# TERM.net
KiCad netlist of a schematic drawn in Altium Designer
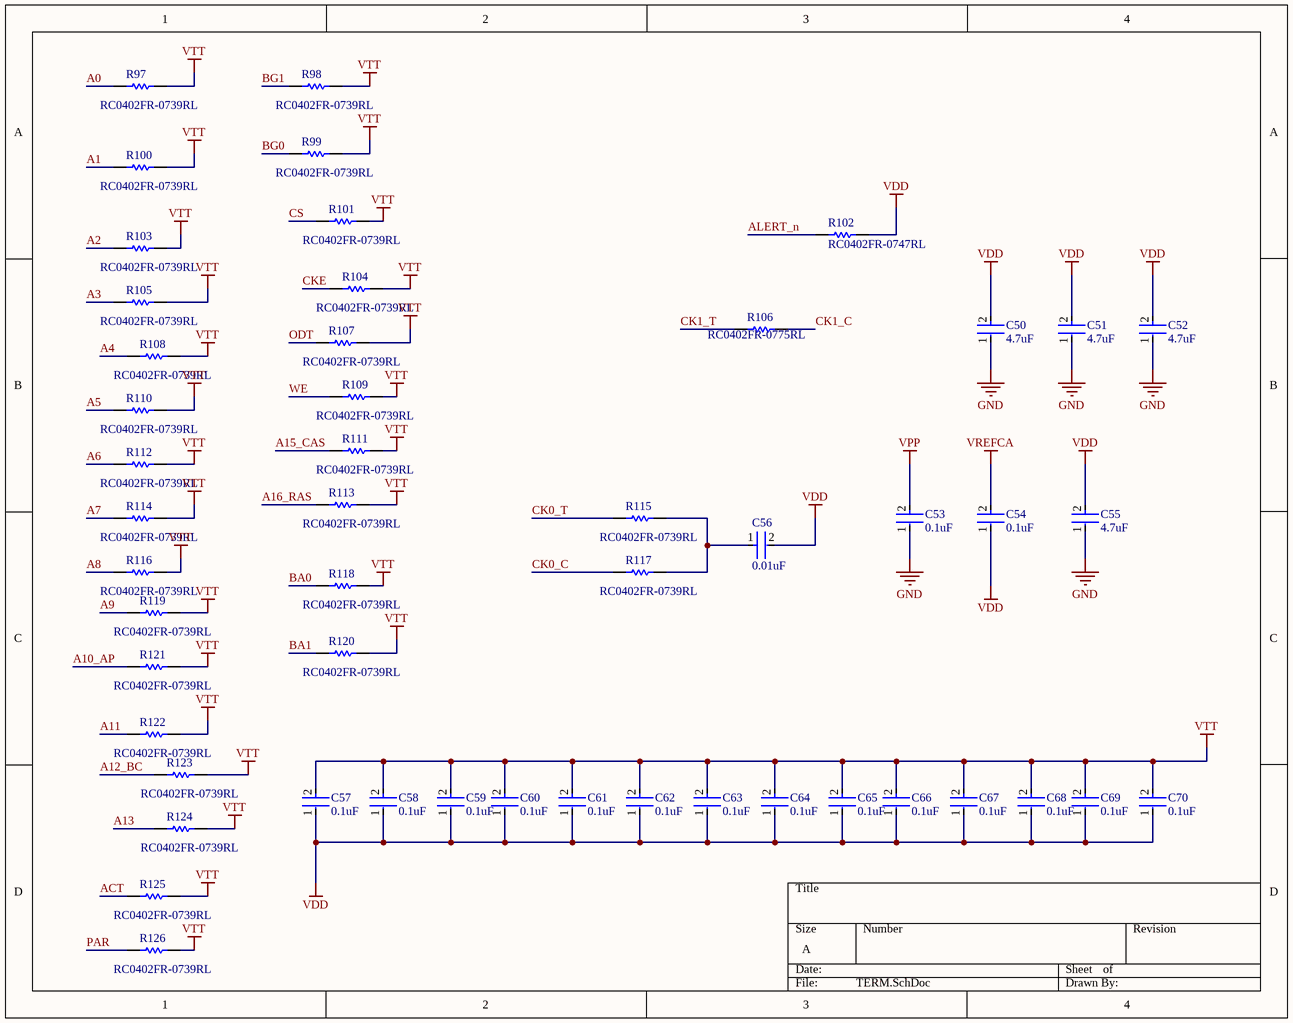
[diagram p0: TERM.SchDoc]

(export (version "E")
  (design (tool "Eeschema 10.0.6"))
  (components
    (comp (ref "C50")
      (value "4.7uF")
      (footprint "FP-C1608-080-0_1-IPC_C")
      (description "Multilayer Ceramic Capacitors 4.7μF ±10% 16V X5R SMD 0603")
      (fields (field (name "TOLERANCE") "10%") (field (name "VOLTAGE") "16V"))
      (libsource (lib "Altium Content Vault") (part "236180d848d6139a670b325ea6854c9"))
    )
    (comp (ref "C51")
      (value "4.7uF")
      (footprint "FP-C1608-080-0_1-IPC_C")
      (description "Multilayer Ceramic Capacitors 4.7μF ±10% 16V X5R SMD 0603")
      (fields (field (name "TOLERANCE") "10%") (field (name "VOLTAGE") "16V"))
      (libsource (lib "Altium Content Vault") (part "236180d848d6139a670b325ea6854c9"))
    )
    (comp (ref "C52")
      (value "4.7uF")
      (footprint "FP-C1608-080-0_1-IPC_C")
      (description "Multilayer Ceramic Capacitors 4.7μF ±10% 16V X5R SMD 0603")
      (fields (field (name "TOLERANCE") "10%") (field (name "VOLTAGE") "16V"))
      (libsource (lib "Altium Content Vault") (part "236180d848d6139a670b325ea6854c9"))
    )
    (comp (ref "C53")
      (value "0.1uF")
      (footprint "FP-GRM15-MFG")
      (description "CAP CER 0.1UF 16V X7R 0402")
      (fields (field (name "MANUFACTURER PART NUMBER") "GRM155R71C104KA88D") (field (name "TOLERANCE") "10%"))
      (libsource (lib "Altium Content Vault") (part "236180d848d6139a670b325ea6854c9"))
    )
    (comp (ref "C54")
      (value "0.1uF")
      (footprint "FP-GRM15-MFG")
      (description "CAP CER 0.1UF 16V X7R 0402")
      (fields (field (name "MANUFACTURER PART NUMBER") "GRM155R71C104KA88D") (field (name "TOLERANCE") "10%"))
      (libsource (lib "Altium Content Vault") (part "236180d848d6139a670b325ea6854c9"))
    )
    (comp (ref "C55")
      (value "4.7uF")
      (footprint "FP-C1608-080-0_1-IPC_C")
      (description "Multilayer Ceramic Capacitors 4.7μF ±10% 16V X5R SMD 0603")
      (fields (field (name "TOLERANCE") "10%") (field (name "VOLTAGE") "16V"))
      (libsource (lib "Altium Content Vault") (part "236180d848d6139a670b325ea6854c9"))
    )
    (comp (ref "C56")
      (value "0.01uF")
      (footprint "FP-GRM155-0_05-IPC_C")
      (description "Chip Multilayer Ceramic Capacitors for General Purpose, 0402, 10000pF, X7R, 15%, 10%, 50V")
      (fields (field (name "TOLERANCE") "10%") (field (name "VOLTAGE") "25V"))
      (libsource (lib "Altium Content Vault") (part "02cd4be3c70576c341d710602a673aa"))
    )
    (comp (ref "C57")
      (value "0.1uF")
      (footprint "FP-GRM15-MFG")
      (description "CAP CER 0.1UF 16V X7R 0402")
      (fields (field (name "MANUFACTURER PART NUMBER") "GRM155R71C104KA88D") (field (name "TOLERANCE") "10%"))
      (libsource (lib "Altium Content Vault") (part "236180d848d6139a670b325ea6854c9"))
    )
    (comp (ref "C58")
      (value "0.1uF")
      (footprint "FP-GRM15-MFG")
      (description "CAP CER 0.1UF 16V X7R 0402")
      (fields (field (name "MANUFACTURER PART NUMBER") "GRM155R71C104KA88D") (field (name "TOLERANCE") "10%"))
      (libsource (lib "Altium Content Vault") (part "236180d848d6139a670b325ea6854c9"))
    )
    (comp (ref "C59")
      (value "0.1uF")
      (footprint "FP-GRM15-MFG")
      (description "CAP CER 0.1UF 16V X7R 0402")
      (fields (field (name "MANUFACTURER PART NUMBER") "GRM155R71C104KA88D") (field (name "TOLERANCE") "10%"))
      (libsource (lib "Altium Content Vault") (part "236180d848d6139a670b325ea6854c9"))
    )
    (comp (ref "C60")
      (value "0.1uF")
      (footprint "FP-GRM15-MFG")
      (description "CAP CER 0.1UF 16V X7R 0402")
      (fields (field (name "MANUFACTURER PART NUMBER") "GRM155R71C104KA88D") (field (name "TOLERANCE") "10%"))
      (libsource (lib "Altium Content Vault") (part "236180d848d6139a670b325ea6854c9"))
    )
    (comp (ref "C61")
      (value "0.1uF")
      (footprint "FP-GRM15-MFG")
      (description "CAP CER 0.1UF 16V X7R 0402")
      (fields (field (name "MANUFACTURER PART NUMBER") "GRM155R71C104KA88D") (field (name "TOLERANCE") "10%"))
      (libsource (lib "Altium Content Vault") (part "236180d848d6139a670b325ea6854c9"))
    )
    (comp (ref "C62")
      (value "0.1uF")
      (footprint "FP-GRM15-MFG")
      (description "CAP CER 0.1UF 16V X7R 0402")
      (fields (field (name "MANUFACTURER PART NUMBER") "GRM155R71C104KA88D") (field (name "TOLERANCE") "10%"))
      (libsource (lib "Altium Content Vault") (part "236180d848d6139a670b325ea6854c9"))
    )
    (comp (ref "C63")
      (value "0.1uF")
      (footprint "FP-GRM15-MFG")
      (description "CAP CER 0.1UF 16V X7R 0402")
      (fields (field (name "MANUFACTURER PART NUMBER") "GRM155R71C104KA88D") (field (name "TOLERANCE") "10%"))
      (libsource (lib "Altium Content Vault") (part "236180d848d6139a670b325ea6854c9"))
    )
    (comp (ref "C64")
      (value "0.1uF")
      (footprint "FP-GRM15-MFG")
      (description "CAP CER 0.1UF 16V X7R 0402")
      (fields (field (name "MANUFACTURER PART NUMBER") "GRM155R71C104KA88D") (field (name "TOLERANCE") "10%"))
      (libsource (lib "Altium Content Vault") (part "236180d848d6139a670b325ea6854c9"))
    )
    (comp (ref "C65")
      (value "0.1uF")
      (footprint "FP-GRM15-MFG")
      (description "CAP CER 0.1UF 16V X7R 0402")
      (fields (field (name "MANUFACTURER PART NUMBER") "GRM155R71C104KA88D") (field (name "TOLERANCE") "10%"))
      (libsource (lib "Altium Content Vault") (part "236180d848d6139a670b325ea6854c9"))
    )
    (comp (ref "C66")
      (value "0.1uF")
      (footprint "FP-GRM15-MFG")
      (description "CAP CER 0.1UF 16V X7R 0402")
      (fields (field (name "MANUFACTURER PART NUMBER") "GRM155R71C104KA88D") (field (name "TOLERANCE") "10%"))
      (libsource (lib "Altium Content Vault") (part "236180d848d6139a670b325ea6854c9"))
    )
    (comp (ref "C67")
      (value "0.1uF")
      (footprint "FP-GRM15-MFG")
      (description "CAP CER 0.1UF 16V X7R 0402")
      (fields (field (name "MANUFACTURER PART NUMBER") "GRM155R71C104KA88D") (field (name "TOLERANCE") "10%"))
      (libsource (lib "Altium Content Vault") (part "236180d848d6139a670b325ea6854c9"))
    )
    (comp (ref "C68")
      (value "0.1uF")
      (footprint "FP-GRM15-MFG")
      (description "CAP CER 0.1UF 16V X7R 0402")
      (fields (field (name "MANUFACTURER PART NUMBER") "GRM155R71C104KA88D") (field (name "TOLERANCE") "10%"))
      (libsource (lib "Altium Content Vault") (part "236180d848d6139a670b325ea6854c9"))
    )
    (comp (ref "C69")
      (value "0.1uF")
      (footprint "FP-GRM15-MFG")
      (description "CAP CER 0.1UF 16V X7R 0402")
      (fields (field (name "MANUFACTURER PART NUMBER") "GRM155R71C104KA88D") (field (name "TOLERANCE") "10%"))
      (libsource (lib "Altium Content Vault") (part "236180d848d6139a670b325ea6854c9"))
    )
    (comp (ref "C70")
      (value "0.1uF")
      (footprint "FP-GRM15-MFG")
      (description "CAP CER 0.1UF 16V X7R 0402")
      (fields (field (name "MANUFACTURER PART NUMBER") "GRM155R71C104KA88D") (field (name "TOLERANCE") "10%"))
      (libsource (lib "Altium Content Vault") (part "236180d848d6139a670b325ea6854c9"))
    )
    (comp (ref "R97")
      (value "RC0402FR-0739RL")
      (footprint "RESC1005X40X25LL05T10")
      (fields (field (name "MANUFACTURER") "Yageo / Phycomp"))
      (libsource (lib "Altium Content Vault") (part "RES"))
    )
    (comp (ref "R98")
      (value "RC0402FR-0739RL")
      (footprint "RESC1005X40X25LL05T10")
      (fields (field (name "MANUFACTURER") "Yageo / Phycomp"))
      (libsource (lib "Altium Content Vault") (part "RES"))
    )
    (comp (ref "R99")
      (value "RC0402FR-0739RL")
      (footprint "RESC1005X40X25LL05T10")
      (fields (field (name "MANUFACTURER") "Yageo / Phycomp"))
      (libsource (lib "Altium Content Vault") (part "RES"))
    )
    (comp (ref "R100")
      (value "RC0402FR-0739RL")
      (footprint "RESC1005X40X25LL05T10")
      (fields (field (name "MANUFACTURER") "Yageo / Phycomp"))
      (libsource (lib "Altium Content Vault") (part "RES"))
    )
    (comp (ref "R101")
      (value "RC0402FR-0739RL")
      (footprint "RESC1005X40X25LL05T10")
      (fields (field (name "MANUFACTURER") "Yageo / Phycomp"))
      (libsource (lib "Altium Content Vault") (part "RES"))
    )
    (comp (ref "R102")
      (value "RC0402FR-0747RL")
      (footprint "RESC1005X40X25LL05T10")
      (fields (field (name "MANUFACTURER") "Yageo / Phycomp"))
      (libsource (lib "Altium Content Vault") (part "RES"))
    )
    (comp (ref "R103")
      (value "RC0402FR-0739RL")
      (footprint "RESC1005X40X25LL05T10")
      (fields (field (name "MANUFACTURER") "Yageo / Phycomp"))
      (libsource (lib "Altium Content Vault") (part "RES"))
    )
    (comp (ref "R104")
      (value "RC0402FR-0739RL")
      (footprint "RESC1005X40X25LL05T10")
      (fields (field (name "MANUFACTURER") "Yageo / Phycomp"))
      (libsource (lib "Altium Content Vault") (part "RES"))
    )
    (comp (ref "R105")
      (value "RC0402FR-0739RL")
      (footprint "RESC1005X40X25LL05T10")
      (fields (field (name "MANUFACTURER") "Yageo / Phycomp"))
      (libsource (lib "Altium Content Vault") (part "RES"))
    )
    (comp (ref "R106")
      (value "RC0402FR-0775RL")
      (footprint "RESC1005X40X25LL05T10")
      (fields (field (name "MANUFACTURER") "Yageo / Phycomp"))
      (libsource (lib "Altium Content Vault") (part "RES"))
    )
    (comp (ref "R107")
      (value "RC0402FR-0739RL")
      (footprint "RESC1005X40X25LL05T10")
      (fields (field (name "MANUFACTURER") "Yageo / Phycomp"))
      (libsource (lib "Altium Content Vault") (part "RES"))
    )
    (comp (ref "R108")
      (value "RC0402FR-0739RL")
      (footprint "RESC1005X40X25LL05T10")
      (fields (field (name "MANUFACTURER") "Yageo / Phycomp"))
      (libsource (lib "Altium Content Vault") (part "RES"))
    )
    (comp (ref "R109")
      (value "RC0402FR-0739RL")
      (footprint "RESC1005X40X25LL05T10")
      (fields (field (name "MANUFACTURER") "Yageo / Phycomp"))
      (libsource (lib "Altium Content Vault") (part "RES"))
    )
    (comp (ref "R110")
      (value "RC0402FR-0739RL")
      (footprint "RESC1005X40X25LL05T10")
      (fields (field (name "MANUFACTURER") "Yageo / Phycomp"))
      (libsource (lib "Altium Content Vault") (part "RES"))
    )
    (comp (ref "R111")
      (value "RC0402FR-0739RL")
      (footprint "RESC1005X40X25LL05T10")
      (fields (field (name "MANUFACTURER") "Yageo / Phycomp"))
      (libsource (lib "Altium Content Vault") (part "RES"))
    )
    (comp (ref "R112")
      (value "RC0402FR-0739RL")
      (footprint "RESC1005X40X25LL05T10")
      (fields (field (name "MANUFACTURER") "Yageo / Phycomp"))
      (libsource (lib "Altium Content Vault") (part "RES"))
    )
    (comp (ref "R113")
      (value "RC0402FR-0739RL")
      (footprint "RESC1005X40X25LL05T10")
      (fields (field (name "MANUFACTURER") "Yageo / Phycomp"))
      (libsource (lib "Altium Content Vault") (part "RES"))
    )
    (comp (ref "R114")
      (value "RC0402FR-0739RL")
      (footprint "RESC1005X40X25LL05T10")
      (fields (field (name "MANUFACTURER") "Yageo / Phycomp"))
      (libsource (lib "Altium Content Vault") (part "RES"))
    )
    (comp (ref "R115")
      (value "RC0402FR-0739RL")
      (footprint "RESC1005X40X25LL05T10")
      (fields (field (name "MANUFACTURER") "Yageo / Phycomp"))
      (libsource (lib "Altium Content Vault") (part "RES"))
    )
    (comp (ref "R116")
      (value "RC0402FR-0739RL")
      (footprint "RESC1005X40X25LL05T10")
      (fields (field (name "MANUFACTURER") "Yageo / Phycomp"))
      (libsource (lib "Altium Content Vault") (part "RES"))
    )
    (comp (ref "R117")
      (value "RC0402FR-0739RL")
      (footprint "RESC1005X40X25LL05T10")
      (fields (field (name "MANUFACTURER") "Yageo / Phycomp"))
      (libsource (lib "Altium Content Vault") (part "RES"))
    )
    (comp (ref "R118")
      (value "RC0402FR-0739RL")
      (footprint "RESC1005X40X25LL05T10")
      (fields (field (name "MANUFACTURER") "Yageo / Phycomp"))
      (libsource (lib "Altium Content Vault") (part "RES"))
    )
    (comp (ref "R119")
      (value "RC0402FR-0739RL")
      (footprint "RESC1005X40X25LL05T10")
      (fields (field (name "MANUFACTURER") "Yageo / Phycomp"))
      (libsource (lib "Altium Content Vault") (part "RES"))
    )
    (comp (ref "R120")
      (value "RC0402FR-0739RL")
      (footprint "RESC1005X40X25LL05T10")
      (fields (field (name "MANUFACTURER") "Yageo / Phycomp"))
      (libsource (lib "Altium Content Vault") (part "RES"))
    )
    (comp (ref "R121")
      (value "RC0402FR-0739RL")
      (footprint "RESC1005X40X25LL05T10")
      (fields (field (name "MANUFACTURER") "Yageo / Phycomp"))
      (libsource (lib "Altium Content Vault") (part "RES"))
    )
    (comp (ref "R122")
      (value "RC0402FR-0739RL")
      (footprint "RESC1005X40X25LL05T10")
      (fields (field (name "MANUFACTURER") "Yageo / Phycomp"))
      (libsource (lib "Altium Content Vault") (part "RES"))
    )
    (comp (ref "R123")
      (value "RC0402FR-0739RL")
      (footprint "RESC1005X40X25LL05T10")
      (fields (field (name "MANUFACTURER") "Yageo / Phycomp"))
      (libsource (lib "Altium Content Vault") (part "RES"))
    )
    (comp (ref "R124")
      (value "RC0402FR-0739RL")
      (footprint "RESC1005X40X25LL05T10")
      (fields (field (name "MANUFACTURER") "Yageo / Phycomp"))
      (libsource (lib "Altium Content Vault") (part "RES"))
    )
    (comp (ref "R125")
      (value "RC0402FR-0739RL")
      (footprint "RESC1005X40X25LL05T10")
      (fields (field (name "MANUFACTURER") "Yageo / Phycomp"))
      (libsource (lib "Altium Content Vault") (part "RES"))
    )
    (comp (ref "R126")
      (value "RC0402FR-0739RL")
      (footprint "RESC1005X40X25LL05T10")
      (fields (field (name "MANUFACTURER") "Yageo / Phycomp"))
      (libsource (lib "Altium Content Vault") (part "RES"))
    )
  )
  (nets
    (net (code "1") (name "/A0") (class "Default")
      (node (ref "R97") (pin "1") (pinfunction "1_1") (pintype "passive"))
    )
    (net (code "2") (name "/A1") (class "Default")
      (node (ref "R100") (pin "1") (pinfunction "1_1") (pintype "passive"))
    )
    (net (code "3") (name "/A2") (class "Default")
      (node (ref "R103") (pin "1") (pinfunction "1_1") (pintype "passive"))
    )
    (net (code "4") (name "/A3") (class "Default")
      (node (ref "R105") (pin "1") (pinfunction "1_1") (pintype "passive"))
    )
    (net (code "5") (name "/A4") (class "Default")
      (node (ref "R108") (pin "1") (pinfunction "1_1") (pintype "passive"))
    )
    (net (code "6") (name "/A5") (class "Default")
      (node (ref "R110") (pin "1") (pinfunction "1_1") (pintype "passive"))
    )
    (net (code "7") (name "/A6") (class "Default")
      (node (ref "R112") (pin "1") (pinfunction "1_1") (pintype "passive"))
    )
    (net (code "8") (name "/A7") (class "Default")
      (node (ref "R114") (pin "1") (pinfunction "1_1") (pintype "passive"))
    )
    (net (code "9") (name "/A8") (class "Default")
      (node (ref "R116") (pin "1") (pinfunction "1_1") (pintype "passive"))
    )
    (net (code "10") (name "/A9") (class "Default")
      (node (ref "R119") (pin "1") (pinfunction "1_1") (pintype "passive"))
    )
    (net (code "11") (name "/A10_AP") (class "Default")
      (node (ref "R121") (pin "1") (pinfunction "1_1") (pintype "passive"))
    )
    (net (code "12") (name "/A11") (class "Default")
      (node (ref "R122") (pin "1") (pinfunction "1_1") (pintype "passive"))
    )
    (net (code "13") (name "/A12_BC") (class "Default")
      (node (ref "R123") (pin "1") (pinfunction "1_1") (pintype "passive"))
    )
    (net (code "14") (name "/A13") (class "Default")
      (node (ref "R124") (pin "1") (pinfunction "1_1") (pintype "passive"))
    )
    (net (code "15") (name "/A15_CAS") (class "Default")
      (node (ref "R111") (pin "1") (pinfunction "1_1") (pintype "passive"))
    )
    (net (code "16") (name "/A16_RAS") (class "Default")
      (node (ref "R113") (pin "1") (pinfunction "1_1") (pintype "passive"))
    )
    (net (code "17") (name "/ACT") (class "Default")
      (node (ref "R125") (pin "1") (pinfunction "1_1") (pintype "passive"))
    )
    (net (code "18") (name "/ALERT_n") (class "Default")
      (node (ref "R102") (pin "1") (pinfunction "1_1") (pintype "passive"))
    )
    (net (code "19") (name "/BA0") (class "Default")
      (node (ref "R118") (pin "1") (pinfunction "1_1") (pintype "passive"))
    )
    (net (code "20") (name "/BA1") (class "Default")
      (node (ref "R120") (pin "1") (pinfunction "1_1") (pintype "passive"))
    )
    (net (code "21") (name "/BG0") (class "Default")
      (node (ref "R99") (pin "1") (pinfunction "1_1") (pintype "passive"))
    )
    (net (code "22") (name "/BG1") (class "Default")
      (node (ref "R98") (pin "1") (pinfunction "1_1") (pintype "passive"))
    )
    (net (code "23") (name "/CK0_C") (class "Default")
      (node (ref "R117") (pin "1") (pinfunction "1_1") (pintype "passive"))
    )
    (net (code "24") (name "/CK0_T") (class "Default")
      (node (ref "R115") (pin "1") (pinfunction "1_1") (pintype "passive"))
    )
    (net (code "25") (name "/CK1_C") (class "Default")
      (node (ref "R106") (pin "2") (pinfunction "2_2") (pintype "passive"))
    )
    (net (code "26") (name "/CK1_T") (class "Default")
      (node (ref "R106") (pin "1") (pinfunction "1_1") (pintype "passive"))
    )
    (net (code "27") (name "/CKE") (class "Default")
      (node (ref "R104") (pin "1") (pinfunction "1_1") (pintype "passive"))
    )
    (net (code "28") (name "/CS") (class "Default")
      (node (ref "R101") (pin "1") (pinfunction "1_1") (pintype "passive"))
    )
    (net (code "29") (name "/ODT") (class "Default")
      (node (ref "R107") (pin "1") (pinfunction "1_1") (pintype "passive"))
    )
    (net (code "30") (name "/PAR") (class "Default")
      (node (ref "R126") (pin "1") (pinfunction "1_1") (pintype "passive"))
    )
    (net (code "31") (name "/WE") (class "Default")
      (node (ref "R109") (pin "1") (pinfunction "1_1") (pintype "passive"))
    )
    (net (code "32") (name "GND") (class "Default")
      (node (ref "C50") (pin "1") (pinfunction "1_1") (pintype "passive"))
      (node (ref "C51") (pin "1") (pinfunction "1_1") (pintype "passive"))
      (node (ref "C52") (pin "1") (pinfunction "1_1") (pintype "passive"))
      (node (ref "C53") (pin "1") (pinfunction "1_1") (pintype "passive"))
      (node (ref "C55") (pin "1") (pinfunction "1_1") (pintype "passive"))
    )
    (net (code "33") (name "Net-(C56-Pad1)") (class "Default")
      (node (ref "C56") (pin "1") (pinfunction "1_1") (pintype "passive"))
      (node (ref "R115") (pin "2") (pinfunction "2_2") (pintype "passive"))
      (node (ref "R117") (pin "2") (pinfunction "2_2") (pintype "passive"))
    )
    (net (code "34") (name "VDD") (class "Default")
      (node (ref "C50") (pin "2") (pinfunction "2_2") (pintype "passive"))
      (node (ref "C51") (pin "2") (pinfunction "2_2") (pintype "passive"))
      (node (ref "C52") (pin "2") (pinfunction "2_2") (pintype "passive"))
      (node (ref "C54") (pin "1") (pinfunction "1_1") (pintype "passive"))
      (node (ref "C55") (pin "2") (pinfunction "2_2") (pintype "passive"))
      (node (ref "C56") (pin "2") (pinfunction "2_2") (pintype "passive"))
      (node (ref "C57") (pin "1") (pinfunction "1_1") (pintype "passive"))
      (node (ref "C58") (pin "1") (pinfunction "1_1") (pintype "passive"))
      (node (ref "C59") (pin "1") (pinfunction "1_1") (pintype "passive"))
      (node (ref "C60") (pin "1") (pinfunction "1_1") (pintype "passive"))
      (node (ref "C61") (pin "1") (pinfunction "1_1") (pintype "passive"))
      (node (ref "C62") (pin "1") (pinfunction "1_1") (pintype "passive"))
      (node (ref "C63") (pin "1") (pinfunction "1_1") (pintype "passive"))
      (node (ref "C64") (pin "1") (pinfunction "1_1") (pintype "passive"))
      (node (ref "C65") (pin "1") (pinfunction "1_1") (pintype "passive"))
      (node (ref "C66") (pin "1") (pinfunction "1_1") (pintype "passive"))
      (node (ref "C67") (pin "1") (pinfunction "1_1") (pintype "passive"))
      (node (ref "C68") (pin "1") (pinfunction "1_1") (pintype "passive"))
      (node (ref "C69") (pin "1") (pinfunction "1_1") (pintype "passive"))
      (node (ref "C70") (pin "1") (pinfunction "1_1") (pintype "passive"))
      (node (ref "R102") (pin "2") (pinfunction "2_2") (pintype "passive"))
    )
    (net (code "35") (name "VPP") (class "Default")
      (node (ref "C53") (pin "2") (pinfunction "2_2") (pintype "passive"))
    )
    (net (code "36") (name "VREFCA") (class "Default")
      (node (ref "C54") (pin "2") (pinfunction "2_2") (pintype "passive"))
    )
    (net (code "37") (name "VTT") (class "Default")
      (node (ref "C57") (pin "2") (pinfunction "2_2") (pintype "passive"))
      (node (ref "C58") (pin "2") (pinfunction "2_2") (pintype "passive"))
      (node (ref "C59") (pin "2") (pinfunction "2_2") (pintype "passive"))
      (node (ref "C60") (pin "2") (pinfunction "2_2") (pintype "passive"))
      (node (ref "C61") (pin "2") (pinfunction "2_2") (pintype "passive"))
      (node (ref "C62") (pin "2") (pinfunction "2_2") (pintype "passive"))
      (node (ref "C63") (pin "2") (pinfunction "2_2") (pintype "passive"))
      (node (ref "C64") (pin "2") (pinfunction "2_2") (pintype "passive"))
      (node (ref "C65") (pin "2") (pinfunction "2_2") (pintype "passive"))
      (node (ref "C66") (pin "2") (pinfunction "2_2") (pintype "passive"))
      (node (ref "C67") (pin "2") (pinfunction "2_2") (pintype "passive"))
      (node (ref "C68") (pin "2") (pinfunction "2_2") (pintype "passive"))
      (node (ref "C69") (pin "2") (pinfunction "2_2") (pintype "passive"))
      (node (ref "C70") (pin "2") (pinfunction "2_2") (pintype "passive"))
      (node (ref "R100") (pin "2") (pinfunction "2_2") (pintype "passive"))
      (node (ref "R101") (pin "2") (pinfunction "2_2") (pintype "passive"))
      (node (ref "R103") (pin "2") (pinfunction "2_2") (pintype "passive"))
      (node (ref "R104") (pin "2") (pinfunction "2_2") (pintype "passive"))
      (node (ref "R105") (pin "2") (pinfunction "2_2") (pintype "passive"))
      (node (ref "R107") (pin "2") (pinfunction "2_2") (pintype "passive"))
      (node (ref "R108") (pin "2") (pinfunction "2_2") (pintype "passive"))
      (node (ref "R109") (pin "2") (pinfunction "2_2") (pintype "passive"))
      (node (ref "R110") (pin "2") (pinfunction "2_2") (pintype "passive"))
      (node (ref "R111") (pin "2") (pinfunction "2_2") (pintype "passive"))
      (node (ref "R112") (pin "2") (pinfunction "2_2") (pintype "passive"))
      (node (ref "R113") (pin "2") (pinfunction "2_2") (pintype "passive"))
      (node (ref "R114") (pin "2") (pinfunction "2_2") (pintype "passive"))
      (node (ref "R116") (pin "2") (pinfunction "2_2") (pintype "passive"))
      (node (ref "R118") (pin "2") (pinfunction "2_2") (pintype "passive"))
      (node (ref "R119") (pin "2") (pinfunction "2_2") (pintype "passive"))
      (node (ref "R120") (pin "2") (pinfunction "2_2") (pintype "passive"))
      (node (ref "R121") (pin "2") (pinfunction "2_2") (pintype "passive"))
      (node (ref "R122") (pin "2") (pinfunction "2_2") (pintype "passive"))
      (node (ref "R123") (pin "2") (pinfunction "2_2") (pintype "passive"))
      (node (ref "R124") (pin "2") (pinfunction "2_2") (pintype "passive"))
      (node (ref "R125") (pin "2") (pinfunction "2_2") (pintype "passive"))
      (node (ref "R126") (pin "2") (pinfunction "2_2") (pintype "passive"))
      (node (ref "R97") (pin "2") (pinfunction "2_2") (pintype "passive"))
      (node (ref "R98") (pin "2") (pinfunction "2_2") (pintype "passive"))
      (node (ref "R99") (pin "2") (pinfunction "2_2") (pintype "passive"))
    )
  )
)
